# Relay_Channel.net
KiCad netlist of a schematic drawn in Altium Designer
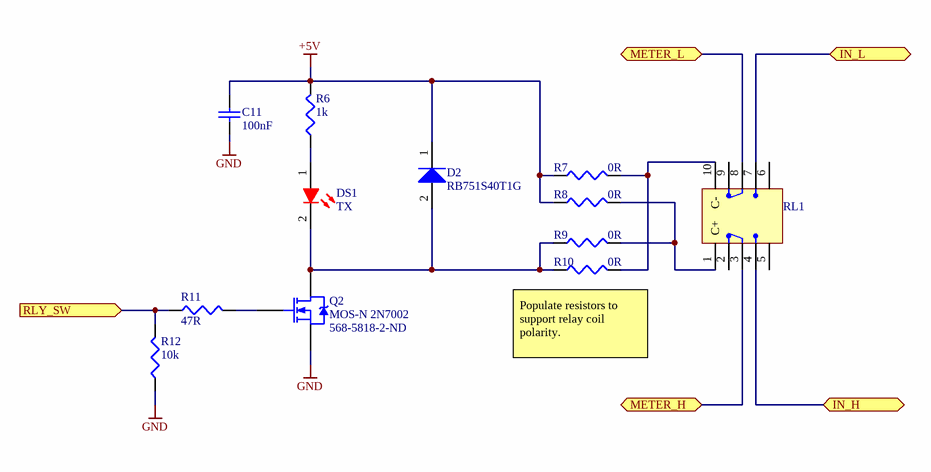
[diagram p0: Relay Channel.SchDoc]

(export (version "E")
  (design (tool "Eeschema 10.0.6"))
  (components
    (comp (ref "C11")
      (value "100nF")
      (footprint "0603")
      (description "Ceramic Chip Capacitor - Standard")
      (fields (field (name "Comment") "C0603") (field (name "PUBLISHER") "Altium Limited"))
      (libsource (lib "MainLib") (part "C0603"))
    )
    (comp (ref "D2")
      (value "RB751S40T1G")
      (footprint "ONSC-SOD-523-2-502-01_C_V")
      (description "Schottky Barrier Diode, 2-Pin SOD-523, Pb-Free, Tape and Reel")
      (fields (field (name "MANUFACTURER") "On Semiconductor"))
      (libsource (lib "Altium Content Vault") (part "ONSC-D-K1A2-2"))
    )
    (comp (ref "DS1")
      (value "TX")
      (footprint "TOSH-0603LED_RED_V")
      (description "LED, Red 0603 (1608) 63mCd")
      (fields (field (name "MANUFACTURER") "Toshiba") (field (name "PARTNUMBER") "TLSU1008A(T04)"))
      (libsource (lib "Altium Content Vault") (part "CMP-0444-00001-1"))
    )
    (comp (ref "Q2")
      (value "MOS-N 2N7002")
      (footprint "SOT-23B_N")
      (description "N-MOSFET 2N7002 NXP")
      (fields
        (field (name "SUPPLIER PART NUMBER 1") "568-5818-2-ND")
        (field (name "PUBLISHER") "Altium Limited")
      )
      (libsource (lib "MainLib") (part "MOS-N 2N7002"))
    )
    (comp (ref "R6")
      (value "1k")
      (footprint "0603")
      (description "Resistor")
      (libsource (lib "MainLib") (part "Resistor"))
    )
    (comp (ref "R7")
      (value "0R")
      (footprint "0603")
      (description "Resistor")
      (libsource (lib "MainLib") (part "Resistor"))
    )
    (comp (ref "R8")
      (value "0R")
      (footprint "0603")
      (description "Resistor")
      (libsource (lib "MainLib") (part "Resistor"))
    )
    (comp (ref "R9")
      (value "0R")
      (footprint "0603")
      (description "Resistor")
      (libsource (lib "MainLib") (part "Resistor"))
    )
    (comp (ref "R10")
      (value "0R")
      (footprint "0603")
      (description "Resistor")
      (libsource (lib "MainLib") (part "Resistor"))
    )
    (comp (ref "R11")
      (value "47R")
      (footprint "0603")
      (description "Resistor")
      (libsource (lib "MainLib") (part "Resistor"))
    )
    (comp (ref "R12")
      (value "10k")
      (footprint "0603")
      (description "Resistor")
      (libsource (lib "MainLib") (part "Resistor"))
    )
    (comp (ref "RL1")
      (value "Relay - PS-5")
      (footprint "PS-5 Relay")
      (description "Relay Small Signal")
      (libsource (lib "MainLib") (part "Relay - PS-5"))
    )
  )
  (nets
    (net (code "1") (name "+5V") (class "Default")
      (node (ref "C11") (pin "2") (pinfunction "2_2") (pintype "passive"))
      (node (ref "D2") (pin "1") (pinfunction "K_1") (pintype "passive"))
      (node (ref "R6") (pin "2") (pinfunction "2_2") (pintype "passive"))
      (node (ref "R7") (pin "1") (pinfunction "1_1") (pintype "passive"))
      (node (ref "R8") (pin "1") (pinfunction "1_1") (pintype "passive"))
    )
    (net (code "2") (name "/IN_H") (class "Default")
      (node (ref "RL1") (pin "4") (pinfunction "4_4") (pintype "passive"))
    )
    (net (code "3") (name "/IN_L") (class "Default")
      (node (ref "RL1") (pin "7") (pinfunction "7_7") (pintype "passive"))
    )
    (net (code "4") (name "/METER_H") (class "Default")
      (node (ref "RL1") (pin "3") (pinfunction "3_3") (pintype "passive"))
    )
    (net (code "5") (name "/METER_L") (class "Default")
      (node (ref "RL1") (pin "8") (pinfunction "8_8") (pintype "passive"))
    )
    (net (code "6") (name "/RLY_SW") (class "Default")
      (node (ref "R11") (pin "1") (pinfunction "1_1") (pintype "passive"))
      (node (ref "R12") (pin "2") (pinfunction "2_2") (pintype "passive"))
    )
    (net (code "7") (name "GND") (class "Default")
      (node (ref "C11") (pin "1") (pinfunction "1_1") (pintype "passive"))
      (node (ref "Q2") (pin "2") (pinfunction "S_2") (pintype "passive"))
      (node (ref "R12") (pin "1") (pinfunction "1_1") (pintype "passive"))
    )
    (net (code "8") (name "Net-(D2-A)") (class "Default")
      (node (ref "D2") (pin "2") (pinfunction "A_2") (pintype "passive"))
      (node (ref "DS1") (pin "2") (pinfunction "K_2") (pintype "passive"))
      (node (ref "Q2") (pin "3") (pinfunction "D_3") (pintype "passive"))
      (node (ref "R10") (pin "1") (pinfunction "1_1") (pintype "passive"))
      (node (ref "R9") (pin "1") (pinfunction "1_1") (pintype "passive"))
    )
    (net (code "9") (name "Net-(DS1-A)") (class "Default")
      (node (ref "DS1") (pin "1") (pinfunction "A_1") (pintype "passive"))
      (node (ref "R6") (pin "1") (pinfunction "1_1") (pintype "passive"))
    )
    (net (code "10") (name "Net-(Q2-G)") (class "Default")
      (node (ref "Q2") (pin "1") (pinfunction "G_1") (pintype "passive"))
      (node (ref "R11") (pin "2") (pinfunction "2_2") (pintype "passive"))
    )
    (net (code "11") (name "Net-(RL1-C+)") (class "Default")
      (node (ref "R8") (pin "2") (pinfunction "2_2") (pintype "passive"))
      (node (ref "R9") (pin "2") (pinfunction "2_2") (pintype "passive"))
      (node (ref "RL1") (pin "1") (pinfunction "C+_1") (pintype "passive"))
    )
    (net (code "12") (name "Net-(RL1-C-)") (class "Default")
      (node (ref "R10") (pin "2") (pinfunction "2_2") (pintype "passive"))
      (node (ref "R7") (pin "2") (pinfunction "2_2") (pintype "passive"))
      (node (ref "RL1") (pin "10") (pinfunction "C-_10") (pintype "passive"))
    )
    (net (code "13") (name "unconnected-(RL1-Pad2)") (class "Default")
      (node (ref "RL1") (pin "2") (pinfunction "2_2") (pintype "passive"))
    )
    (net (code "14") (name "unconnected-(RL1-Pad5)") (class "Default")
      (node (ref "RL1") (pin "5") (pinfunction "5_5") (pintype "passive"))
    )
    (net (code "15") (name "unconnected-(RL1-Pad6)") (class "Default")
      (node (ref "RL1") (pin "6") (pinfunction "6_6") (pintype "passive"))
    )
    (net (code "16") (name "unconnected-(RL1-Pad9)") (class "Default")
      (node (ref "RL1") (pin "9") (pinfunction "9_9") (pintype "passive"))
    )
  )
)
